# untitled.net
KiCad netlist of a schematic drawn in EAGLE
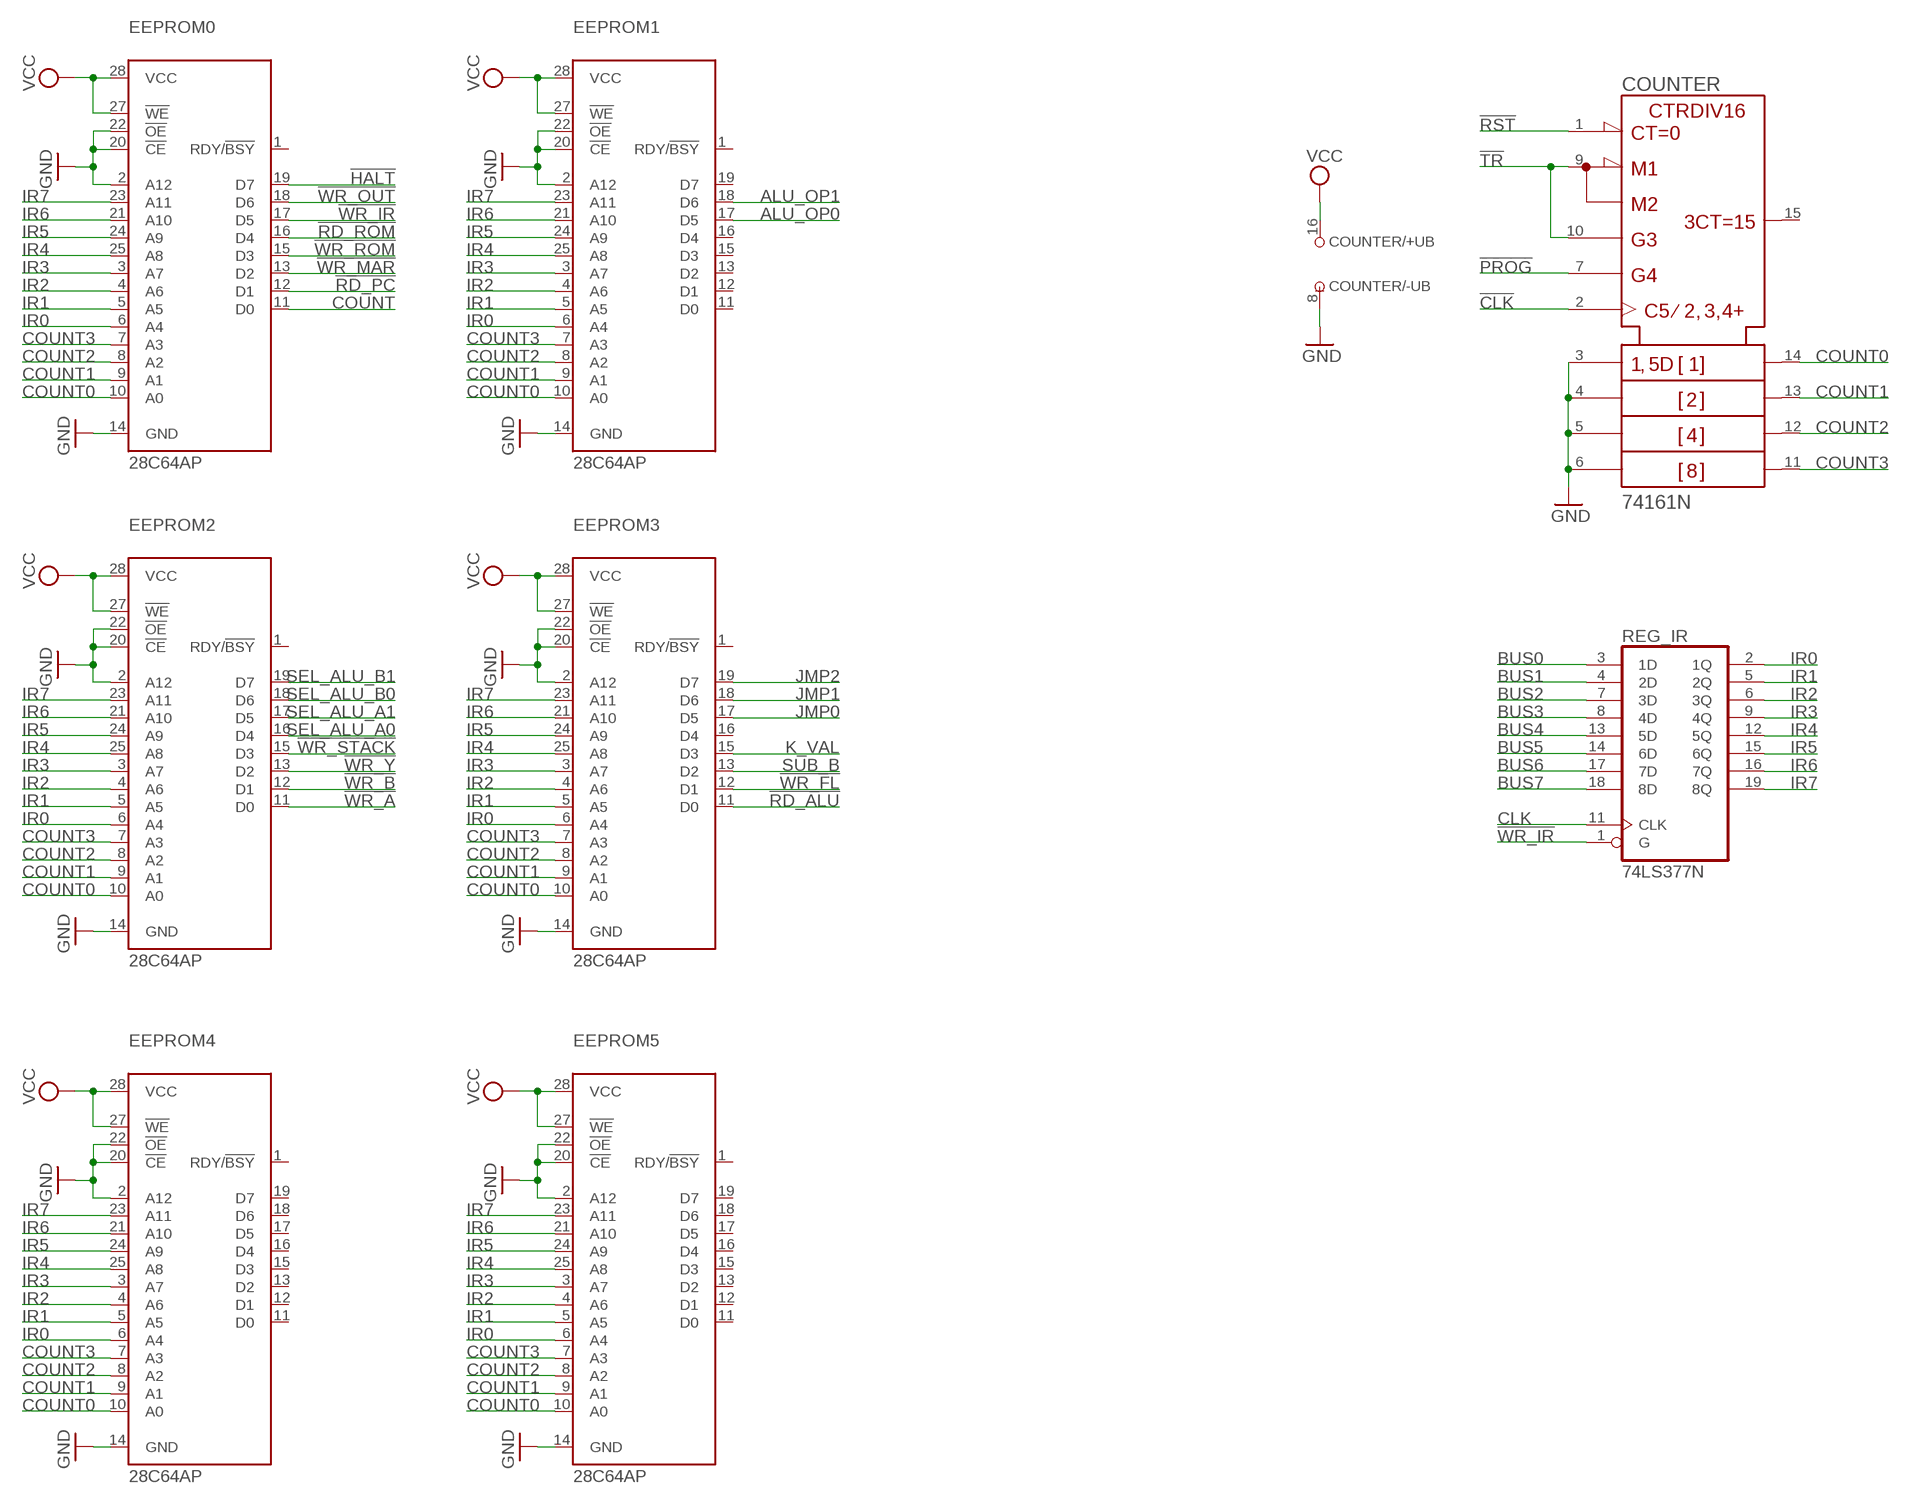
[diagram p0: schematic, sheet 1, part 1 of 2]
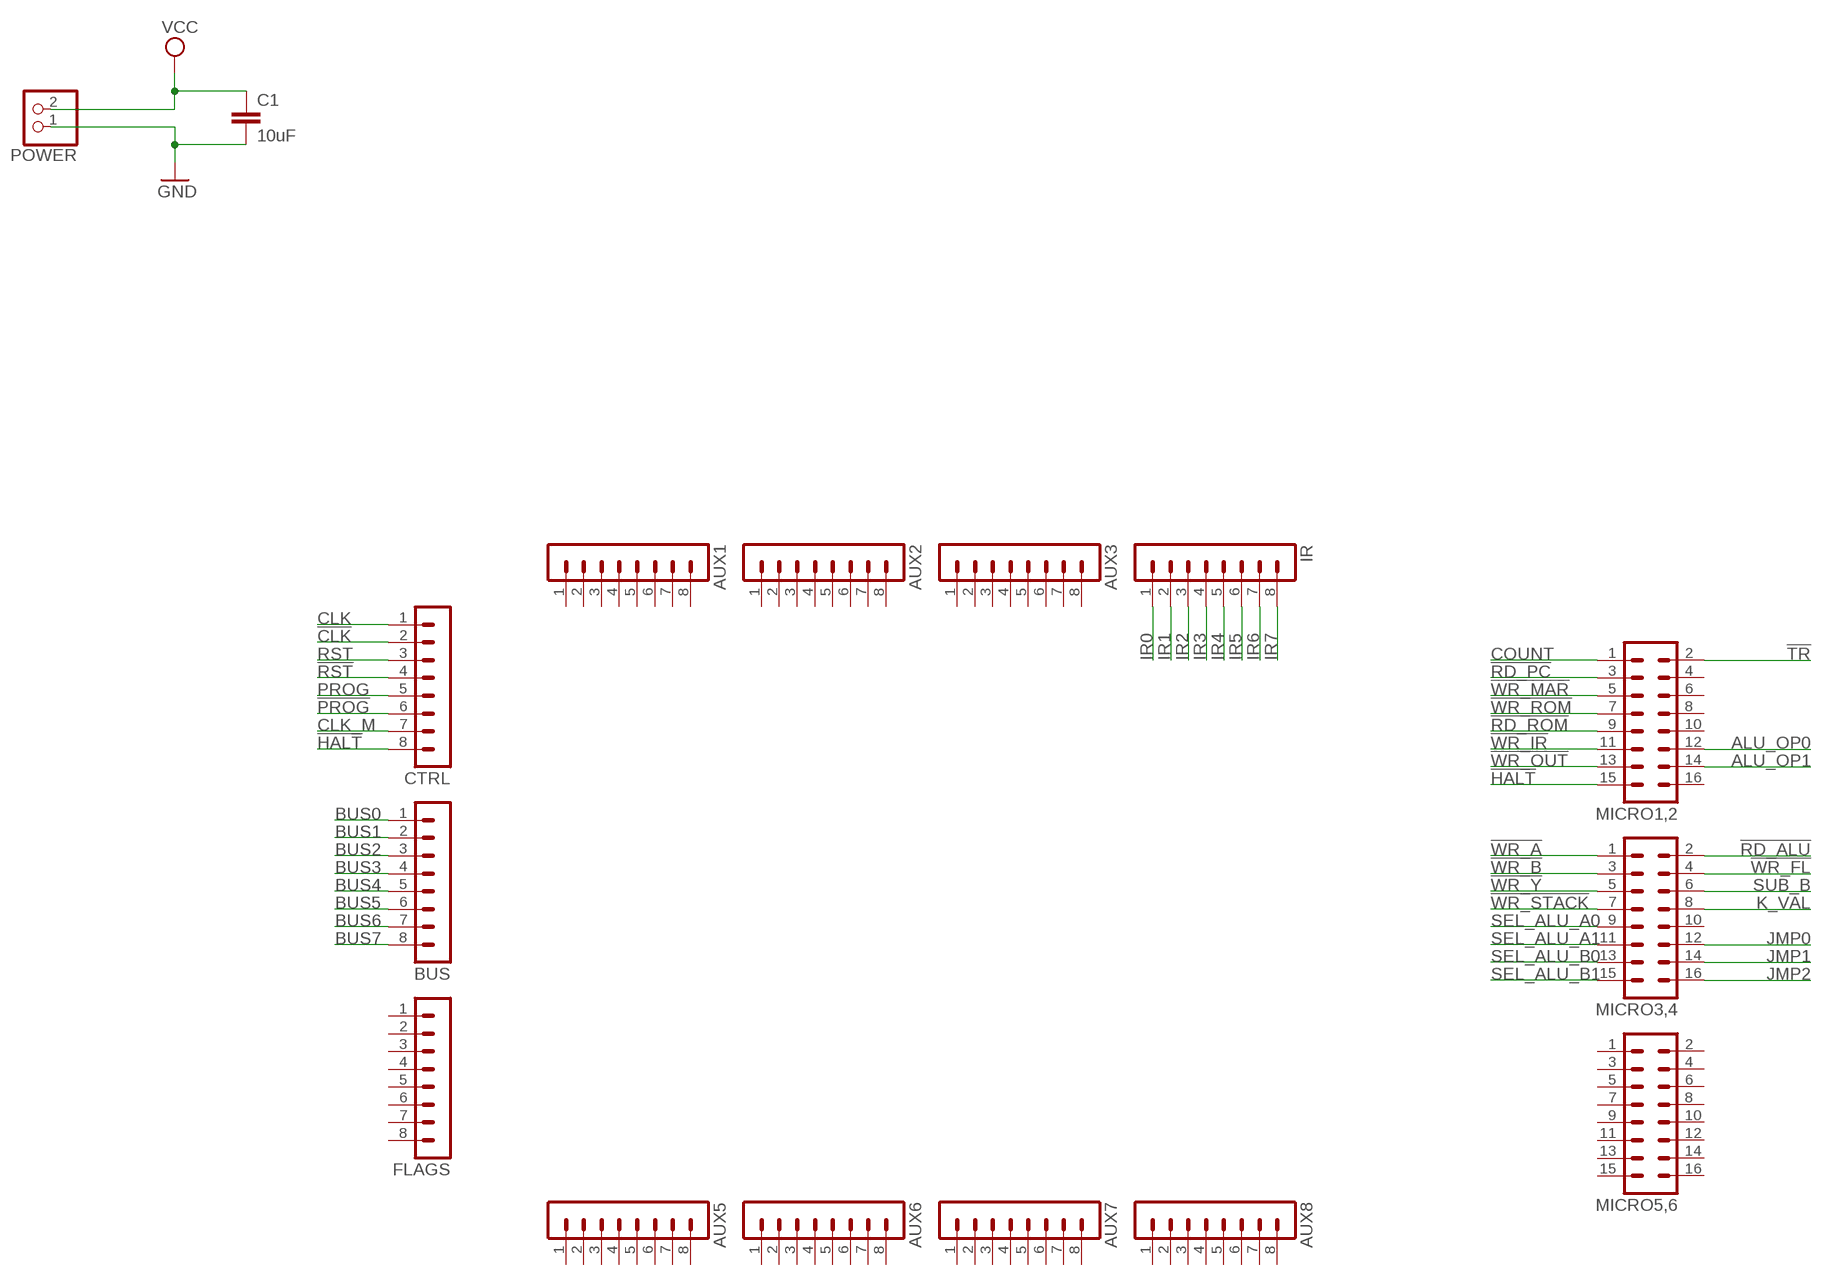
[diagram p1: schematic, sheet 1, part 2 of 2]

(export (version "E")
  (design (tool "Eeschema 10.0.6"))
  (components
    (comp (ref "AUX1")
      (value "MA08-1")
      (footprint "eagle-import:MA08-1")
      (libsource (lib "eagle-import") (part "MA08-1"))
    )
    (comp (ref "AUX2")
      (value "MA08-1")
      (footprint "eagle-import:MA08-1")
      (libsource (lib "eagle-import") (part "MA08-1"))
    )
    (comp (ref "AUX3")
      (value "MA08-1")
      (footprint "eagle-import:MA08-1")
      (libsource (lib "eagle-import") (part "MA08-1"))
    )
    (comp (ref "AUX5")
      (value "MA08-1")
      (footprint "eagle-import:MA08-1")
      (libsource (lib "eagle-import") (part "MA08-1"))
    )
    (comp (ref "AUX6")
      (value "MA08-1")
      (footprint "eagle-import:MA08-1")
      (libsource (lib "eagle-import") (part "MA08-1"))
    )
    (comp (ref "AUX7")
      (value "MA08-1")
      (footprint "eagle-import:MA08-1")
      (libsource (lib "eagle-import") (part "MA08-1"))
    )
    (comp (ref "AUX8")
      (value "MA08-1")
      (footprint "eagle-import:MA08-1")
      (libsource (lib "eagle-import") (part "MA08-1"))
    )
    (comp (ref "BUS")
      (value "MA08-1")
      (footprint "eagle-import:MA08-1")
      (libsource (lib "eagle-import") (part "MA08-1"))
    )
    (comp (ref "C1")
      (value "10uF")
      (footprint "eagle-import:C025-050X050")
      (libsource (lib "eagle-import") (part "C-EU025-050X050"))
    )
    (comp (ref "COUNTER")
      (value "74161N")
      (footprint "eagle-import:DIL16")
      (libsource (lib "eagle-import") (part "74161N"))
    )
    (comp (ref "CTRL")
      (value "MA08-1")
      (footprint "eagle-import:MA08-1")
      (libsource (lib "eagle-import") (part "MA08-1"))
    )
    (comp (ref "EEPROM0")
      (value "28C64AP")
      (footprint "eagle-import:DIL28-6")
      (fields (field (name "MPN") "AT28C64B-15PU"))
      (libsource (lib "eagle-import") (part "2864APC"))
    )
    (comp (ref "EEPROM1")
      (value "28C64AP")
      (footprint "eagle-import:DIL28-6")
      (fields (field (name "MPN") "AT28C64B-15PU"))
      (libsource (lib "eagle-import") (part "2864APC"))
    )
    (comp (ref "EEPROM2")
      (value "28C64AP")
      (footprint "eagle-import:DIL28-6")
      (fields (field (name "MPN") "AT28C64B-15PU"))
      (libsource (lib "eagle-import") (part "2864APC"))
    )
    (comp (ref "EEPROM3")
      (value "28C64AP")
      (footprint "eagle-import:DIL28-6")
      (fields (field (name "MPN") "AT28C64B-15PU"))
      (libsource (lib "eagle-import") (part "2864APC"))
    )
    (comp (ref "EEPROM4")
      (value "28C64AP")
      (footprint "eagle-import:DIL28-6")
      (fields (field (name "MPN") "AT28C64B-15PU"))
      (libsource (lib "eagle-import") (part "2864APC"))
    )
    (comp (ref "EEPROM5")
      (value "28C64AP")
      (footprint "eagle-import:DIL28-6")
      (fields (field (name "MPN") "AT28C64B-15PU"))
      (libsource (lib "eagle-import") (part "2864APC"))
    )
    (comp (ref "FLAGS")
      (value "MA08-1")
      (footprint "eagle-import:MA08-1")
      (libsource (lib "eagle-import") (part "MA08-1"))
    )
    (comp (ref "IR")
      (value "MA08-1")
      (footprint "eagle-import:MA08-1")
      (libsource (lib "eagle-import") (part "MA08-1"))
    )
    (comp (ref "MICRO1,2")
      (value "MA08-2")
      (footprint "eagle-import:MA08-2")
      (libsource (lib "eagle-import") (part "MA08-2"))
    )
    (comp (ref "MICRO3,4")
      (value "MA08-2")
      (footprint "eagle-import:MA08-2")
      (libsource (lib "eagle-import") (part "MA08-2"))
    )
    (comp (ref "MICRO5,6")
      (value "MA08-2")
      (footprint "eagle-import:MA08-2")
      (libsource (lib "eagle-import") (part "MA08-2"))
    )
    (comp (ref "POWER")
      (value "PINHD-1X2")
      (footprint "eagle-import:1X02")
      (libsource (lib "eagle-import") (part "PINHD-1X2"))
    )
    (comp (ref "REG_IR")
      (value "74LS377N")
      (footprint "eagle-import:DIL20")
      (libsource (lib "eagle-import") (part "74377NLS"))
    )
  )
  (nets
    (net (code "1") (name "ALU_OP0") (class "Default")
      (node (ref "EEPROM1") (pin "17") (pinfunction "D5_17") (pintype "tri_state"))
      (node (ref "MICRO1,2") (pin "12") (pinfunction "12_12") (pintype "passive"))
    )
    (net (code "2") (name "ALU_OP1") (class "Default")
      (node (ref "EEPROM1") (pin "18") (pinfunction "D6_18") (pintype "tri_state"))
      (node (ref "MICRO1,2") (pin "14") (pinfunction "14_14") (pintype "passive"))
    )
    (net (code "3") (name "BUS0") (class "Default")
      (node (ref "BUS") (pin "1") (pinfunction "1_1") (pintype "passive"))
      (node (ref "REG_IR") (pin "3") (pinfunction "1D_3") (pintype "input"))
    )
    (net (code "4") (name "BUS1") (class "Default")
      (node (ref "BUS") (pin "2") (pinfunction "2_2") (pintype "passive"))
      (node (ref "REG_IR") (pin "4") (pinfunction "2D_4") (pintype "input"))
    )
    (net (code "5") (name "BUS2") (class "Default")
      (node (ref "BUS") (pin "3") (pinfunction "3_3") (pintype "passive"))
      (node (ref "REG_IR") (pin "7") (pinfunction "3D_7") (pintype "input"))
    )
    (net (code "6") (name "BUS3") (class "Default")
      (node (ref "BUS") (pin "4") (pinfunction "4_4") (pintype "passive"))
      (node (ref "REG_IR") (pin "8") (pinfunction "4D_8") (pintype "input"))
    )
    (net (code "7") (name "BUS4") (class "Default")
      (node (ref "BUS") (pin "5") (pinfunction "5_5") (pintype "passive"))
      (node (ref "REG_IR") (pin "13") (pinfunction "5D_13") (pintype "input"))
    )
    (net (code "8") (name "BUS5") (class "Default")
      (node (ref "BUS") (pin "6") (pinfunction "6_6") (pintype "passive"))
      (node (ref "REG_IR") (pin "14") (pinfunction "6D_14") (pintype "input"))
    )
    (net (code "9") (name "BUS6") (class "Default")
      (node (ref "BUS") (pin "7") (pinfunction "7_7") (pintype "passive"))
      (node (ref "REG_IR") (pin "17") (pinfunction "7D_17") (pintype "input"))
    )
    (net (code "10") (name "BUS7") (class "Default")
      (node (ref "BUS") (pin "8") (pinfunction "8_8") (pintype "passive"))
      (node (ref "REG_IR") (pin "18") (pinfunction "8D_18") (pintype "input"))
    )
    (net (code "11") (name "CLK") (class "Default")
      (node (ref "CTRL") (pin "1") (pinfunction "1_1") (pintype "passive"))
      (node (ref "REG_IR") (pin "11") (pinfunction "CLK_11") (pintype "input"))
    )
    (net (code "12") (name "CLK_M") (class "Default")
      (node (ref "CTRL") (pin "7") (pinfunction "7_7") (pintype "passive"))
    )
    (net (code "13") (name "COUNT") (class "Default")
      (node (ref "EEPROM0") (pin "11") (pinfunction "D0_11") (pintype "tri_state"))
      (node (ref "MICRO1,2") (pin "1") (pinfunction "1_1") (pintype "passive"))
    )
    (net (code "14") (name "COUNT0") (class "Default")
      (node (ref "COUNTER") (pin "14") (pinfunction "QA_14") (pintype "output"))
      (node (ref "EEPROM0") (pin "10") (pinfunction "A0_10") (pintype "input"))
      (node (ref "EEPROM1") (pin "10") (pinfunction "A0_10") (pintype "input"))
      (node (ref "EEPROM2") (pin "10") (pinfunction "A0_10") (pintype "input"))
      (node (ref "EEPROM3") (pin "10") (pinfunction "A0_10") (pintype "input"))
      (node (ref "EEPROM4") (pin "10") (pinfunction "A0_10") (pintype "input"))
      (node (ref "EEPROM5") (pin "10") (pinfunction "A0_10") (pintype "input"))
    )
    (net (code "15") (name "COUNT1") (class "Default")
      (node (ref "COUNTER") (pin "13") (pinfunction "QB_13") (pintype "output"))
      (node (ref "EEPROM0") (pin "9") (pinfunction "A1_9") (pintype "input"))
      (node (ref "EEPROM1") (pin "9") (pinfunction "A1_9") (pintype "input"))
      (node (ref "EEPROM2") (pin "9") (pinfunction "A1_9") (pintype "input"))
      (node (ref "EEPROM3") (pin "9") (pinfunction "A1_9") (pintype "input"))
      (node (ref "EEPROM4") (pin "9") (pinfunction "A1_9") (pintype "input"))
      (node (ref "EEPROM5") (pin "9") (pinfunction "A1_9") (pintype "input"))
    )
    (net (code "16") (name "COUNT2") (class "Default")
      (node (ref "COUNTER") (pin "12") (pinfunction "QC_12") (pintype "output"))
      (node (ref "EEPROM0") (pin "8") (pinfunction "A2_8") (pintype "input"))
      (node (ref "EEPROM1") (pin "8") (pinfunction "A2_8") (pintype "input"))
      (node (ref "EEPROM2") (pin "8") (pinfunction "A2_8") (pintype "input"))
      (node (ref "EEPROM3") (pin "8") (pinfunction "A2_8") (pintype "input"))
      (node (ref "EEPROM4") (pin "8") (pinfunction "A2_8") (pintype "input"))
      (node (ref "EEPROM5") (pin "8") (pinfunction "A2_8") (pintype "input"))
    )
    (net (code "17") (name "COUNT3") (class "Default")
      (node (ref "COUNTER") (pin "11") (pinfunction "QD_11") (pintype "output"))
      (node (ref "EEPROM0") (pin "7") (pinfunction "A3_7") (pintype "input"))
      (node (ref "EEPROM1") (pin "7") (pinfunction "A3_7") (pintype "input"))
      (node (ref "EEPROM2") (pin "7") (pinfunction "A3_7") (pintype "input"))
      (node (ref "EEPROM3") (pin "7") (pinfunction "A3_7") (pintype "input"))
      (node (ref "EEPROM4") (pin "7") (pinfunction "A3_7") (pintype "input"))
      (node (ref "EEPROM5") (pin "7") (pinfunction "A3_7") (pintype "input"))
    )
    (net (code "18") (name "GND") (class "Default")
      (node (ref "C1") (pin "2") (pinfunction "2_2") (pintype "passive"))
      (node (ref "COUNTER") (pin "3") (pinfunction "A_3") (pintype "input"))
      (node (ref "COUNTER") (pin "4") (pinfunction "B_4") (pintype "input"))
      (node (ref "COUNTER") (pin "5") (pinfunction "C_5") (pintype "input"))
      (node (ref "COUNTER") (pin "6") (pinfunction "D_6") (pintype "input"))
      (node (ref "COUNTER") (pin "8") (pinfunction "-UB_8") (pintype "power_in"))
      (node (ref "EEPROM0") (pin "14") (pinfunction "GND_14") (pintype "power_in"))
      (node (ref "EEPROM0") (pin "2") (pinfunction "A12_2") (pintype "input"))
      (node (ref "EEPROM0") (pin "20") (pinfunction "~{CE}_20") (pintype "input"))
      (node (ref "EEPROM0") (pin "22") (pinfunction "~{OE}_22") (pintype "input"))
      (node (ref "EEPROM1") (pin "14") (pinfunction "GND_14") (pintype "power_in"))
      (node (ref "EEPROM1") (pin "2") (pinfunction "A12_2") (pintype "input"))
      (node (ref "EEPROM1") (pin "20") (pinfunction "~{CE}_20") (pintype "input"))
      (node (ref "EEPROM1") (pin "22") (pinfunction "~{OE}_22") (pintype "input"))
      (node (ref "EEPROM2") (pin "14") (pinfunction "GND_14") (pintype "power_in"))
      (node (ref "EEPROM2") (pin "2") (pinfunction "A12_2") (pintype "input"))
      (node (ref "EEPROM2") (pin "20") (pinfunction "~{CE}_20") (pintype "input"))
      (node (ref "EEPROM2") (pin "22") (pinfunction "~{OE}_22") (pintype "input"))
      (node (ref "EEPROM3") (pin "14") (pinfunction "GND_14") (pintype "power_in"))
      (node (ref "EEPROM3") (pin "2") (pinfunction "A12_2") (pintype "input"))
      (node (ref "EEPROM3") (pin "20") (pinfunction "~{CE}_20") (pintype "input"))
      (node (ref "EEPROM3") (pin "22") (pinfunction "~{OE}_22") (pintype "input"))
      (node (ref "EEPROM4") (pin "14") (pinfunction "GND_14") (pintype "power_in"))
      (node (ref "EEPROM4") (pin "2") (pinfunction "A12_2") (pintype "input"))
      (node (ref "EEPROM4") (pin "20") (pinfunction "~{CE}_20") (pintype "input"))
      (node (ref "EEPROM4") (pin "22") (pinfunction "~{OE}_22") (pintype "input"))
      (node (ref "EEPROM5") (pin "14") (pinfunction "GND_14") (pintype "power_in"))
      (node (ref "EEPROM5") (pin "2") (pinfunction "A12_2") (pintype "input"))
      (node (ref "EEPROM5") (pin "20") (pinfunction "~{CE}_20") (pintype "input"))
      (node (ref "EEPROM5") (pin "22") (pinfunction "~{OE}_22") (pintype "input"))
      (node (ref "POWER") (pin "1") (pinfunction "1_1") (pintype "passive"))
    )
    (net (code "19") (name "IR0") (class "Default")
      (node (ref "EEPROM0") (pin "6") (pinfunction "A4_6") (pintype "input"))
      (node (ref "EEPROM1") (pin "6") (pinfunction "A4_6") (pintype "input"))
      (node (ref "EEPROM2") (pin "6") (pinfunction "A4_6") (pintype "input"))
      (node (ref "EEPROM3") (pin "6") (pinfunction "A4_6") (pintype "input"))
      (node (ref "EEPROM4") (pin "6") (pinfunction "A4_6") (pintype "input"))
      (node (ref "EEPROM5") (pin "6") (pinfunction "A4_6") (pintype "input"))
      (node (ref "IR") (pin "1") (pinfunction "1_1") (pintype "passive"))
      (node (ref "REG_IR") (pin "2") (pinfunction "1Q_2") (pintype "output"))
    )
    (net (code "20") (name "IR1") (class "Default")
      (node (ref "EEPROM0") (pin "5") (pinfunction "A5_5") (pintype "input"))
      (node (ref "EEPROM1") (pin "5") (pinfunction "A5_5") (pintype "input"))
      (node (ref "EEPROM2") (pin "5") (pinfunction "A5_5") (pintype "input"))
      (node (ref "EEPROM3") (pin "5") (pinfunction "A5_5") (pintype "input"))
      (node (ref "EEPROM4") (pin "5") (pinfunction "A5_5") (pintype "input"))
      (node (ref "EEPROM5") (pin "5") (pinfunction "A5_5") (pintype "input"))
      (node (ref "IR") (pin "2") (pinfunction "2_2") (pintype "passive"))
      (node (ref "REG_IR") (pin "5") (pinfunction "2Q_5") (pintype "output"))
    )
    (net (code "21") (name "IR2") (class "Default")
      (node (ref "EEPROM0") (pin "4") (pinfunction "A6_4") (pintype "input"))
      (node (ref "EEPROM1") (pin "4") (pinfunction "A6_4") (pintype "input"))
      (node (ref "EEPROM2") (pin "4") (pinfunction "A6_4") (pintype "input"))
      (node (ref "EEPROM3") (pin "4") (pinfunction "A6_4") (pintype "input"))
      (node (ref "EEPROM4") (pin "4") (pinfunction "A6_4") (pintype "input"))
      (node (ref "EEPROM5") (pin "4") (pinfunction "A6_4") (pintype "input"))
      (node (ref "IR") (pin "3") (pinfunction "3_3") (pintype "passive"))
      (node (ref "REG_IR") (pin "6") (pinfunction "3Q_6") (pintype "output"))
    )
    (net (code "22") (name "IR3") (class "Default")
      (node (ref "EEPROM0") (pin "3") (pinfunction "A7_3") (pintype "input"))
      (node (ref "EEPROM1") (pin "3") (pinfunction "A7_3") (pintype "input"))
      (node (ref "EEPROM2") (pin "3") (pinfunction "A7_3") (pintype "input"))
      (node (ref "EEPROM3") (pin "3") (pinfunction "A7_3") (pintype "input"))
      (node (ref "EEPROM4") (pin "3") (pinfunction "A7_3") (pintype "input"))
      (node (ref "EEPROM5") (pin "3") (pinfunction "A7_3") (pintype "input"))
      (node (ref "IR") (pin "4") (pinfunction "4_4") (pintype "passive"))
      (node (ref "REG_IR") (pin "9") (pinfunction "4Q_9") (pintype "output"))
    )
    (net (code "23") (name "IR4") (class "Default")
      (node (ref "EEPROM0") (pin "25") (pinfunction "A8_25") (pintype "input"))
      (node (ref "EEPROM1") (pin "25") (pinfunction "A8_25") (pintype "input"))
      (node (ref "EEPROM2") (pin "25") (pinfunction "A8_25") (pintype "input"))
      (node (ref "EEPROM3") (pin "25") (pinfunction "A8_25") (pintype "input"))
      (node (ref "EEPROM4") (pin "25") (pinfunction "A8_25") (pintype "input"))
      (node (ref "EEPROM5") (pin "25") (pinfunction "A8_25") (pintype "input"))
      (node (ref "IR") (pin "5") (pinfunction "5_5") (pintype "passive"))
      (node (ref "REG_IR") (pin "12") (pinfunction "5Q_12") (pintype "output"))
    )
    (net (code "24") (name "IR5") (class "Default")
      (node (ref "EEPROM0") (pin "24") (pinfunction "A9_24") (pintype "input"))
      (node (ref "EEPROM1") (pin "24") (pinfunction "A9_24") (pintype "input"))
      (node (ref "EEPROM2") (pin "24") (pinfunction "A9_24") (pintype "input"))
      (node (ref "EEPROM3") (pin "24") (pinfunction "A9_24") (pintype "input"))
      (node (ref "EEPROM4") (pin "24") (pinfunction "A9_24") (pintype "input"))
      (node (ref "EEPROM5") (pin "24") (pinfunction "A9_24") (pintype "input"))
      (node (ref "IR") (pin "6") (pinfunction "6_6") (pintype "passive"))
      (node (ref "REG_IR") (pin "15") (pinfunction "6Q_15") (pintype "output"))
    )
    (net (code "25") (name "IR6") (class "Default")
      (node (ref "EEPROM0") (pin "21") (pinfunction "A10_21") (pintype "input"))
      (node (ref "EEPROM1") (pin "21") (pinfunction "A10_21") (pintype "input"))
      (node (ref "EEPROM2") (pin "21") (pinfunction "A10_21") (pintype "input"))
      (node (ref "EEPROM3") (pin "21") (pinfunction "A10_21") (pintype "input"))
      (node (ref "EEPROM4") (pin "21") (pinfunction "A10_21") (pintype "input"))
      (node (ref "EEPROM5") (pin "21") (pinfunction "A10_21") (pintype "input"))
      (node (ref "IR") (pin "7") (pinfunction "7_7") (pintype "passive"))
      (node (ref "REG_IR") (pin "16") (pinfunction "7Q_16") (pintype "output"))
    )
    (net (code "26") (name "IR7") (class "Default")
      (node (ref "EEPROM0") (pin "23") (pinfunction "A11_23") (pintype "input"))
      (node (ref "EEPROM1") (pin "23") (pinfunction "A11_23") (pintype "input"))
      (node (ref "EEPROM2") (pin "23") (pinfunction "A11_23") (pintype "input"))
      (node (ref "EEPROM3") (pin "23") (pinfunction "A11_23") (pintype "input"))
      (node (ref "EEPROM4") (pin "23") (pinfunction "A11_23") (pintype "input"))
      (node (ref "EEPROM5") (pin "23") (pinfunction "A11_23") (pintype "input"))
      (node (ref "IR") (pin "8") (pinfunction "8_8") (pintype "passive"))
      (node (ref "REG_IR") (pin "19") (pinfunction "8Q_19") (pintype "output"))
    )
    (net (code "27") (name "JMP0") (class "Default")
      (node (ref "EEPROM3") (pin "17") (pinfunction "D5_17") (pintype "tri_state"))
      (node (ref "MICRO3,4") (pin "12") (pinfunction "12_12") (pintype "passive"))
    )
    (net (code "28") (name "JMP1") (class "Default")
      (node (ref "EEPROM3") (pin "18") (pinfunction "D6_18") (pintype "tri_state"))
      (node (ref "MICRO3,4") (pin "14") (pinfunction "14_14") (pintype "passive"))
    )
    (net (code "29") (name "JMP2") (class "Default")
      (node (ref "EEPROM3") (pin "19") (pinfunction "D7_19") (pintype "tri_state"))
      (node (ref "MICRO3,4") (pin "16") (pinfunction "16_16") (pintype "passive"))
    )
    (net (code "30") (name "K_VAL") (class "Default")
      (node (ref "EEPROM3") (pin "15") (pinfunction "D3_15") (pintype "tri_state"))
      (node (ref "MICRO3,4") (pin "8") (pinfunction "8_8") (pintype "passive"))
    )
    (net (code "31") (name "PROG") (class "Default")
      (node (ref "CTRL") (pin "5") (pinfunction "5_5") (pintype "passive"))
    )
    (net (code "32") (name "RST") (class "Default")
      (node (ref "CTRL") (pin "3") (pinfunction "3_3") (pintype "passive"))
    )
    (net (code "33") (name "SEL_ALU_A0") (class "Default")
      (node (ref "EEPROM2") (pin "16") (pinfunction "D4_16") (pintype "tri_state"))
      (node (ref "MICRO3,4") (pin "9") (pinfunction "9_9") (pintype "passive"))
    )
    (net (code "34") (name "SEL_ALU_A1") (class "Default")
      (node (ref "EEPROM2") (pin "17") (pinfunction "D5_17") (pintype "tri_state"))
      (node (ref "MICRO3,4") (pin "11") (pinfunction "11_11") (pintype "passive"))
    )
    (net (code "35") (name "SEL_ALU_B0") (class "Default")
      (node (ref "EEPROM2") (pin "18") (pinfunction "D6_18") (pintype "tri_state"))
      (node (ref "MICRO3,4") (pin "13") (pinfunction "13_13") (pintype "passive"))
    )
    (net (code "36") (name "SEL_ALU_B1") (class "Default")
      (node (ref "EEPROM2") (pin "19") (pinfunction "D7_19") (pintype "tri_state"))
      (node (ref "MICRO3,4") (pin "15") (pinfunction "15_15") (pintype "passive"))
    )
    (net (code "37") (name "SUB_B") (class "Default")
      (node (ref "EEPROM3") (pin "13") (pinfunction "D2_13") (pintype "tri_state"))
      (node (ref "MICRO3,4") (pin "6") (pinfunction "6_6") (pintype "passive"))
    )
    (net (code "38") (name "VCC") (class "Default")
      (node (ref "C1") (pin "1") (pinfunction "1_1") (pintype "passive"))
      (node (ref "COUNTER") (pin "16") (pinfunction "+UB_16") (pintype "power_in"))
      (node (ref "EEPROM0") (pin "27") (pinfunction "~{WE}_27") (pintype "input"))
      (node (ref "EEPROM0") (pin "28") (pinfunction "VCC_28") (pintype "power_in"))
      (node (ref "EEPROM1") (pin "27") (pinfunction "~{WE}_27") (pintype "input"))
      (node (ref "EEPROM1") (pin "28") (pinfunction "VCC_28") (pintype "power_in"))
      (node (ref "EEPROM2") (pin "27") (pinfunction "~{WE}_27") (pintype "input"))
      (node (ref "EEPROM2") (pin "28") (pinfunction "VCC_28") (pintype "power_in"))
      (node (ref "EEPROM3") (pin "27") (pinfunction "~{WE}_27") (pintype "input"))
      (node (ref "EEPROM3") (pin "28") (pinfunction "VCC_28") (pintype "power_in"))
      (node (ref "EEPROM4") (pin "27") (pinfunction "~{WE}_27") (pintype "input"))
      (node (ref "EEPROM4") (pin "28") (pinfunction "VCC_28") (pintype "power_in"))
      (node (ref "EEPROM5") (pin "27") (pinfunction "~{WE}_27") (pintype "input"))
      (node (ref "EEPROM5") (pin "28") (pinfunction "VCC_28") (pintype "power_in"))
      (node (ref "POWER") (pin "2") (pinfunction "2_2") (pintype "passive"))
    )
    (net (code "39") (name "unconnected-(AUX1-Pad1)") (class "Default")
      (node (ref "AUX1") (pin "1") (pinfunction "1_1") (pintype "passive"))
    )
    (net (code "40") (name "unconnected-(AUX1-Pad2)") (class "Default")
      (node (ref "AUX1") (pin "2") (pinfunction "2_2") (pintype "passive"))
    )
    (net (code "41") (name "unconnected-(AUX1-Pad3)") (class "Default")
      (node (ref "AUX1") (pin "3") (pinfunction "3_3") (pintype "passive"))
    )
    (net (code "42") (name "unconnected-(AUX1-Pad4)") (class "Default")
      (node (ref "AUX1") (pin "4") (pinfunction "4_4") (pintype "passive"))
    )
    (net (code "43") (name "unconnected-(AUX1-Pad5)") (class "Default")
      (node (ref "AUX1") (pin "5") (pinfunction "5_5") (pintype "passive"))
    )
    (net (code "44") (name "unconnected-(AUX1-Pad6)") (class "Default")
      (node (ref "AUX1") (pin "6") (pinfunction "6_6") (pintype "passive"))
    )
    (net (code "45") (name "unconnected-(AUX1-Pad7)") (class "Default")
      (node (ref "AUX1") (pin "7") (pinfunction "7_7") (pintype "passive"))
    )
    (net (code "46") (name "unconnected-(AUX1-Pad8)") (class "Default")
      (node (ref "AUX1") (pin "8") (pinfunction "8_8") (pintype "passive"))
    )
    (net (code "47") (name "unconnected-(AUX2-Pad1)") (class "Default")
      (node (ref "AUX2") (pin "1") (pinfunction "1_1") (pintype "passive"))
    )
    (net (code "48") (name "unconnected-(AUX2-Pad2)") (class "Default")
      (node (ref "AUX2") (pin "2") (pinfunction "2_2") (pintype "passive"))
    )
    (net (code "49") (name "unconnected-(AUX2-Pad3)") (class "Default")
      (node (ref "AUX2") (pin "3") (pinfunction "3_3") (pintype "passive"))
    )
    (net (code "50") (name "unconnected-(AUX2-Pad4)") (class "Default")
      (node (ref "AUX2") (pin "4") (pinfunction "4_4") (pintype "passive"))
    )
    (net (code "51") (name "unconnected-(AUX2-Pad5)") (class "Default")
      (node (ref "AUX2") (pin "5") (pinfunction "5_5") (pintype "passive"))
    )
    (net (code "52") (name "unconnected-(AUX2-Pad6)") (class "Default")
      (node (ref "AUX2") (pin "6") (pinfunction "6_6") (pintype "passive"))
    )
    (net (code "53") (name "unconnected-(AUX2-Pad7)") (class "Default")
      (node (ref "AUX2") (pin "7") (pinfunction "7_7") (pintype "passive"))
    )
    (net (code "54") (name "unconnected-(AUX2-Pad8)") (class "Default")
      (node (ref "AUX2") (pin "8") (pinfunction "8_8") (pintype "passive"))
    )
    (net (code "55") (name "unconnected-(AUX3-Pad1)") (class "Default")
      (node (ref "AUX3") (pin "1") (pinfunction "1_1") (pintype "passive"))
    )
    (net (code "56") (name "unconnected-(AUX3-Pad2)") (class "Default")
      (node (ref "AUX3") (pin "2") (pinfunction "2_2") (pintype "passive"))
    )
    (net (code "57") (name "unconnected-(AUX3-Pad3)") (class "Default")
      (node (ref "AUX3") (pin "3") (pinfunction "3_3") (pintype "passive"))
    )
    (net (code "58") (name "unconnected-(AUX3-Pad4)") (class "Default")
      (node (ref "AUX3") (pin "4") (pinfunction "4_4") (pintype "passive"))
    )
    (net (code "59") (name "unconnected-(AUX3-Pad5)") (class "Default")
      (node (ref "AUX3") (pin "5") (pinfunction "5_5") (pintype "passive"))
    )
    (net (code "60") (name "unconnected-(AUX3-Pad6)") (class "Default")
      (node (ref "AUX3") (pin "6") (pinfunction "6_6") (pintype "passive"))
    )
    (net (code "61") (name "unconnected-(AUX3-Pad7)") (class "Default")
      (node (ref "AUX3") (pin "7") (pinfunction "7_7") (pintype "passive"))
    )
    (net (code "62") (name "unconnected-(AUX3-Pad8)") (class "Default")
      (node (ref "AUX3") (pin "8") (pinfunction "8_8") (pintype "passive"))
    )
    (net (code "63") (name "unconnected-(AUX5-Pad1)") (class "Default")
      (node (ref "AUX5") (pin "1") (pinfunction "1_1") (pintype "passive"))
    )
    (net (code "64") (name "unconnected-(AUX5-Pad2)") (class "Default")
      (node (ref "AUX5") (pin "2") (pinfunction "2_2") (pintype "passive"))
    )
    (net (code "65") (name "unconnected-(AUX5-Pad3)") (class "Default")
      (node (ref "AUX5") (pin "3") (pinfunction "3_3") (pintype "passive"))
    )
    (net (code "66") (name "unconnected-(AUX5-Pad4)") (class "Default")
      (node (ref "AUX5") (pin "4") (pinfunction "4_4") (pintype "passive"))
    )
    (net (code "67") (name "unconnected-(AUX5-Pad5)") (class "Default")
      (node (ref "AUX5") (pin "5") (pinfunction "5_5") (pintype "passive"))
    )
    (net (code "68") (name "unconnected-(AUX5-Pad6)") (class "Default")
      (node (ref "AUX5") (pin "6") (pinfunction "6_6") (pintype "passive"))
    )
    (net (code "69") (name "unconnected-(AUX5-Pad7)") (class "Default")
      (node (ref "AUX5") (pin "7") (pinfunction "7_7") (pintype "passive"))
    )
    (net (code "70") (name "unconnected-(AUX5-Pad8)") (class "Default")
      (node (ref "AUX5") (pin "8") (pinfunction "8_8") (pintype "passive"))
    )
    (net (code "71") (name "unconnected-(AUX6-Pad1)") (class "Default")
      (node (ref "AUX6") (pin "1") (pinfunction "1_1") (pintype "passive"))
    )
    (net (code "72") (name "unconnected-(AUX6-Pad2)") (class "Default")
      (node (ref "AUX6") (pin "2") (pinfunction "2_2") (pintype "passive"))
    )
    (net (code "73") (name "unconnected-(AUX6-Pad3)") (class "Default")
      (node (ref "AUX6") (pin "3") (pinfunction "3_3") (pintype "passive"))
    )
    (net (code "74") (name "unconnected-(AUX6-Pad4)") (class "Default")
      (node (ref "AUX6") (pin "4") (pinfunction "4_4") (pintype "passive"))
    )
    (net (code "75") (name "unconnected-(AUX6-Pad5)") (class "Default")
      (node (ref "AUX6") (pin "5") (pinfunction "5_5") (pintype "passive"))
    )
    (net (code "76") (name "unconnected-(AUX6-Pad6)") (class "Default")
      (node (ref "AUX6") (pin "6") (pinfunction "6_6") (pintype "passive"))
    )
    (net (code "77") (name "unconnected-(AUX6-Pad7)") (class "Default")
      (node (ref "AUX6") (pin "7") (pinfunction "7_7") (pintype "passive"))
    )
    (net (code "78") (name "unconnected-(AUX6-Pad8)") (class "Default")
      (node (ref "AUX6") (pin "8") (pinfunction "8_8") (pintype "passive"))
    )
    (net (code "79") (name "unconnected-(AUX7-Pad1)") (class "Default")
      (node (ref "AUX7") (pin "1") (pinfunction "1_1") (pintype "passive"))
    )
    (net (code "80") (name "unconnected-(AUX7-Pad2)") (class "Default")
      (node (ref "AUX7") (pin "2") (pinfunction "2_2") (pintype "passive"))
    )
    (net (code "81") (name "unconnected-(AUX7-Pad3)") (class "Default")
      (node (ref "AUX7") (pin "3") (pinfunction "3_3") (pintype "passive"))
    )
    (net (code "82") (name "unconnected-(AUX7-Pad4)") (class "Default")
      (node (ref "AUX7") (pin "4") (pinfunction "4_4") (pintype "passive"))
    )
    (net (code "83") (name "unconnected-(AUX7-Pad5)") (class "Default")
      (node (ref "AUX7") (pin "5") (pinfunction "5_5") (pintype "passive"))
    )
    (net (code "84") (name "unconnected-(AUX7-Pad6)") (class "Default")
      (node (ref "AUX7") (pin "6") (pinfunction "6_6") (pintype "passive"))
    )
    (net (code "85") (name "unconnected-(AUX7-Pad7)") (class "Default")
      (node (ref "AUX7") (pin "7") (pinfunction "7_7") (pintype "passive"))
    )
    (net (code "86") (name "unconnected-(AUX7-Pad8)") (class "Default")
      (node (ref "AUX7") (pin "8") (pinfunction "8_8") (pintype "passive"))
    )
    (net (code "87") (name "unconnected-(AUX8-Pad1)") (class "Default")
      (node (ref "AUX8") (pin "1") (pinfunction "1_1") (pintype "passive"))
    )
    (net (code "88") (name "unconnected-(AUX8-Pad2)") (class "Default")
      (node (ref "AUX8") (pin "2") (pinfunction "2_2") (pintype "passive"))
    )
    (net (code "89") (name "unconnected-(AUX8-Pad3)") (class "Default")
      (node (ref "AUX8") (pin "3") (pinfunction "3_3") (pintype "passive"))
    )
    (net (code "90") (name "unconnected-(AUX8-Pad4)") (class "Default")
      (node (ref "AUX8") (pin "4") (pinfunction "4_4") (pintype "passive"))
    )
    (net (code "91") (name "unconnected-(AUX8-Pad5)") (class "Default")
      (node (ref "AUX8") (pin "5") (pinfunction "5_5") (pintype "passive"))
    )
    (net (code "92") (name "unconnected-(AUX8-Pad6)") (class "Default")
      (node (ref "AUX8") (pin "6") (pinfunction "6_6") (pintype "passive"))
    )
    (net (code "93") (name "unconnected-(AUX8-Pad7)") (class "Default")
      (node (ref "AUX8") (pin "7") (pinfunction "7_7") (pintype "passive"))
    )
    (net (code "94") (name "unconnected-(AUX8-Pad8)") (class "Default")
      (node (ref "AUX8") (pin "8") (pinfunction "8_8") (pintype "passive"))
    )
    (net (code "95") (name "unconnected-(COUNTERC-RCO-Pad15)") (class "Default")
      (node (ref "COUNTER") (pin "15") (pinfunction "RCO_15") (pintype "output"))
    )
    (net (code "96") (name "unconnected-(EEPROM0-RDY{slash}~{BSY}-Pad1)") (class "Default")
      (node (ref "EEPROM0") (pin "1") (pinfunction "RDY/~{BSY}_1") (pintype "output"))
    )
    (net (code "97") (name "unconnected-(EEPROM1-D0-Pad11)") (class "Default")
      (node (ref "EEPROM1") (pin "11") (pinfunction "D0_11") (pintype "tri_state"))
    )
    (net (code "98") (name "unconnected-(EEPROM1-D1-Pad12)") (class "Default")
      (node (ref "EEPROM1") (pin "12") (pinfunction "D1_12") (pintype "tri_state"))
    )
    (net (code "99") (name "unconnected-(EEPROM1-D2-Pad13)") (class "Default")
      (node (ref "EEPROM1") (pin "13") (pinfunction "D2_13") (pintype "tri_state"))
    )
    (net (code "100") (name "unconnected-(EEPROM1-D3-Pad15)") (class "Default")
      (node (ref "EEPROM1") (pin "15") (pinfunction "D3_15") (pintype "tri_state"))
    )
    (net (code "101") (name "unconnected-(EEPROM1-D4-Pad16)") (class "Default")
      (node (ref "EEPROM1") (pin "16") (pinfunction "D4_16") (pintype "tri_state"))
    )
    (net (code "102") (name "unconnected-(EEPROM1-D7-Pad19)") (class "Default")
      (node (ref "EEPROM1") (pin "19") (pinfunction "D7_19") (pintype "tri_state"))
    )
    (net (code "103") (name "unconnected-(EEPROM1-RDY{slash}~{BSY}-Pad1)") (class "Default")
      (node (ref "EEPROM1") (pin "1") (pinfunction "RDY/~{BSY}_1") (pintype "output"))
    )
    (net (code "104") (name "unconnected-(EEPROM2-RDY{slash}~{BSY}-Pad1)") (class "Default")
      (node (ref "EEPROM2") (pin "1") (pinfunction "RDY/~{BSY}_1") (pintype "output"))
    )
    (net (code "105") (name "unconnected-(EEPROM3-D4-Pad16)") (class "Default")
      (node (ref "EEPROM3") (pin "16") (pinfunction "D4_16") (pintype "tri_state"))
    )
    (net (code "106") (name "unconnected-(EEPROM3-RDY{slash}~{BSY}-Pad1)") (class "Default")
      (node (ref "EEPROM3") (pin "1") (pinfunction "RDY/~{BSY}_1") (pintype "output"))
    )
    (net (code "107") (name "unconnected-(EEPROM4-D0-Pad11)") (class "Default")
      (node (ref "EEPROM4") (pin "11") (pinfunction "D0_11") (pintype "tri_state"))
    )
    (net (code "108") (name "unconnected-(EEPROM4-D1-Pad12)") (class "Default")
      (node (ref "EEPROM4") (pin "12") (pinfunction "D1_12") (pintype "tri_state"))
    )
    (net (code "109") (name "unconnected-(EEPROM4-D2-Pad13)") (class "Default")
      (node (ref "EEPROM4") (pin "13") (pinfunction "D2_13") (pintype "tri_state"))
    )
    (net (code "110") (name "unconnected-(EEPROM4-D3-Pad15)") (class "Default")
      (node (ref "EEPROM4") (pin "15") (pinfunction "D3_15") (pintype "tri_state"))
    )
    (net (code "111") (name "unconnected-(EEPROM4-D4-Pad16)") (class "Default")
      (node (ref "EEPROM4") (pin "16") (pinfunction "D4_16") (pintype "tri_state"))
    )
    (net (code "112") (name "unconnected-(EEPROM4-D5-Pad17)") (class "Default")
      (node (ref "EEPROM4") (pin "17") (pinfunction "D5_17") (pintype "tri_state"))
    )
    (net (code "113") (name "unconnected-(EEPROM4-D6-Pad18)") (class "Default")
      (node (ref "EEPROM4") (pin "18") (pinfunction "D6_18") (pintype "tri_state"))
    )
    (net (code "114") (name "unconnected-(EEPROM4-D7-Pad19)") (class "Default")
      (node (ref "EEPROM4") (pin "19") (pinfunction "D7_19") (pintype "tri_state"))
    )
    (net (code "115") (name "unconnected-(EEPROM4-RDY{slash}~{BSY}-Pad1)") (class "Default")
      (node (ref "EEPROM4") (pin "1") (pinfunction "RDY/~{BSY}_1") (pintype "output"))
    )
    (net (code "116") (name "unconnected-(EEPROM5-D0-Pad11)") (class "Default")
      (node (ref "EEPROM5") (pin "11") (pinfunction "D0_11") (pintype "tri_state"))
    )
    (net (code "117") (name "unconnected-(EEPROM5-D1-Pad12)") (class "Default")
      (node (ref "EEPROM5") (pin "12") (pinfunction "D1_12") (pintype "tri_state"))
    )
    (net (code "118") (name "unconnected-(EEPROM5-D2-Pad13)") (class "Default")
      (node (ref "EEPROM5") (pin "13") (pinfunction "D2_13") (pintype "tri_state"))
    )
    (net (code "119") (name "unconnected-(EEPROM5-D3-Pad15)") (class "Default")
      (node (ref "EEPROM5") (pin "15") (pinfunction "D3_15") (pintype "tri_state"))
    )
    (net (code "120") (name "unconnected-(EEPROM5-D4-Pad16)") (class "Default")
      (node (ref "EEPROM5") (pin "16") (pinfunction "D4_16") (pintype "tri_state"))
    )
    (net (code "121") (name "unconnected-(EEPROM5-D5-Pad17)") (class "Default")
      (node (ref "EEPROM5") (pin "17") (pinfunction "D5_17") (pintype "tri_state"))
    )
    (net (code "122") (name "unconnected-(EEPROM5-D6-Pad18)") (class "Default")
      (node (ref "EEPROM5") (pin "18") (pinfunction "D6_18") (pintype "tri_state"))
    )
    (net (code "123") (name "unconnected-(EEPROM5-D7-Pad19)") (class "Default")
      (node (ref "EEPROM5") (pin "19") (pinfunction "D7_19") (pintype "tri_state"))
    )
    (net (code "124") (name "unconnected-(EEPROM5-RDY{slash}~{BSY}-Pad1)") (class "Default")
      (node (ref "EEPROM5") (pin "1") (pinfunction "RDY/~{BSY}_1") (pintype "output"))
    )
    (net (code "125") (name "unconnected-(FLAGS-Pad1)") (class "Default")
      (node (ref "FLAGS") (pin "1") (pinfunction "1_1") (pintype "passive"))
    )
    (net (code "126") (name "unconnected-(FLAGS-Pad2)") (class "Default")
      (node (ref "FLAGS") (pin "2") (pinfunction "2_2") (pintype "passive"))
    )
    (net (code "127") (name "unconnected-(FLAGS-Pad3)") (class "Default")
      (node (ref "FLAGS") (pin "3") (pinfunction "3_3") (pintype "passive"))
    )
    (net (code "128") (name "unconnected-(FLAGS-Pad4)") (class "Default")
      (node (ref "FLAGS") (pin "4") (pinfunction "4_4") (pintype "passive"))
    )
    (net (code "129") (name "unconnected-(FLAGS-Pad5)") (class "Default")
      (node (ref "FLAGS") (pin "5") (pinfunction "5_5") (pintype "passive"))
    )
    (net (code "130") (name "unconnected-(FLAGS-Pad6)") (class "Default")
      (node (ref "FLAGS") (pin "6") (pinfunction "6_6") (pintype "passive"))
    )
    (net (code "131") (name "unconnected-(FLAGS-Pad7)") (class "Default")
      (node (ref "FLAGS") (pin "7") (pinfunction "7_7") (pintype "passive"))
    )
    (net (code "132") (name "unconnected-(FLAGS-Pad8)") (class "Default")
      (node (ref "FLAGS") (pin "8") (pinfunction "8_8") (pintype "passive"))
    )
    (net (code "133") (name "unconnected-(MICRO1,2-Pad4)") (class "Default")
      (node (ref "MICRO1,2") (pin "4") (pinfunction "4_4") (pintype "passive"))
    )
    (net (code "134") (name "unconnected-(MICRO1,2-Pad6)") (class "Default")
      (node (ref "MICRO1,2") (pin "6") (pinfunction "6_6") (pintype "passive"))
    )
    (net (code "135") (name "unconnected-(MICRO1,2-Pad8)") (class "Default")
      (node (ref "MICRO1,2") (pin "8") (pinfunction "8_8") (pintype "passive"))
    )
    (net (code "136") (name "unconnected-(MICRO1,2-Pad10)") (class "Default")
      (node (ref "MICRO1,2") (pin "10") (pinfunction "10_10") (pintype "passive"))
    )
    (net (code "137") (name "unconnected-(MICRO1,2-Pad16)") (class "Default")
      (node (ref "MICRO1,2") (pin "16") (pinfunction "16_16") (pintype "passive"))
    )
    (net (code "138") (name "unconnected-(MICRO3,4-Pad10)") (class "Default")
      (node (ref "MICRO3,4") (pin "10") (pinfunction "10_10") (pintype "passive"))
    )
    (net (code "139") (name "unconnected-(MICRO5,6-Pad1)") (class "Default")
      (node (ref "MICRO5,6") (pin "1") (pinfunction "1_1") (pintype "passive"))
    )
    (net (code "140") (name "unconnected-(MICRO5,6-Pad2)") (class "Default")
      (node (ref "MICRO5,6") (pin "2") (pinfunction "2_2") (pintype "passive"))
    )
    (net (code "141") (name "unconnected-(MICRO5,6-Pad3)") (class "Default")
      (node (ref "MICRO5,6") (pin "3") (pinfunction "3_3") (pintype "passive"))
    )
    (net (code "142") (name "unconnected-(MICRO5,6-Pad4)") (class "Default")
      (node (ref "MICRO5,6") (pin "4") (pinfunction "4_4") (pintype "passive"))
    )
    (net (code "143") (name "unconnected-(MICRO5,6-Pad5)") (class "Default")
      (node (ref "MICRO5,6") (pin "5") (pinfunction "5_5") (pintype "passive"))
    )
    (net (code "144") (name "unconnected-(MICRO5,6-Pad6)") (class "Default")
      (node (ref "MICRO5,6") (pin "6") (pinfunction "6_6") (pintype "passive"))
    )
    (net (code "145") (name "unconnected-(MICRO5,6-Pad7)") (class "Default")
      (node (ref "MICRO5,6") (pin "7") (pinfunction "7_7") (pintype "passive"))
    )
    (net (code "146") (name "unconnected-(MICRO5,6-Pad8)") (class "Default")
      (node (ref "MICRO5,6") (pin "8") (pinfunction "8_8") (pintype "passive"))
    )
    (net (code "147") (name "unconnected-(MICRO5,6-Pad9)") (class "Default")
      (node (ref "MICRO5,6") (pin "9") (pinfunction "9_9") (pintype "passive"))
    )
    (net (code "148") (name "unconnected-(MICRO5,6-Pad10)") (class "Default")
      (node (ref "MICRO5,6") (pin "10") (pinfunction "10_10") (pintype "passive"))
    )
    (net (code "149") (name "unconnected-(MICRO5,6-Pad11)") (class "Default")
      (node (ref "MICRO5,6") (pin "11") (pinfunction "11_11") (pintype "passive"))
    )
    (net (code "150") (name "unconnected-(MICRO5,6-Pad12)") (class "Default")
      (node (ref "MICRO5,6") (pin "12") (pinfunction "12_12") (pintype "passive"))
    )
    (net (code "151") (name "unconnected-(MICRO5,6-Pad13)") (class "Default")
      (node (ref "MICRO5,6") (pin "13") (pinfunction "13_13") (pintype "passive"))
    )
    (net (code "152") (name "unconnected-(MICRO5,6-Pad14)") (class "Default")
      (node (ref "MICRO5,6") (pin "14") (pinfunction "14_14") (pintype "passive"))
    )
    (net (code "153") (name "unconnected-(MICRO5,6-Pad15)") (class "Default")
      (node (ref "MICRO5,6") (pin "15") (pinfunction "15_15") (pintype "passive"))
    )
    (net (code "154") (name "unconnected-(MICRO5,6-Pad16)") (class "Default")
      (node (ref "MICRO5,6") (pin "16") (pinfunction "16_16") (pintype "passive"))
    )
    (net (code "155") (name "~{CLK}") (class "Default")
      (node (ref "COUNTER") (pin "2") (pinfunction "CLK_2") (pintype "input"))
      (node (ref "CTRL") (pin "2") (pinfunction "2_2") (pintype "passive"))
    )
    (net (code "156") (name "~{HALT}") (class "Default")
      (node (ref "CTRL") (pin "8") (pinfunction "8_8") (pintype "passive"))
      (node (ref "EEPROM0") (pin "19") (pinfunction "D7_19") (pintype "tri_state"))
      (node (ref "MICRO1,2") (pin "15") (pinfunction "15_15") (pintype "passive"))
    )
    (net (code "157") (name "~{PROG}") (class "Default")
      (node (ref "COUNTER") (pin "7") (pinfunction "ENP_7") (pintype "input"))
      (node (ref "CTRL") (pin "6") (pinfunction "6_6") (pintype "passive"))
    )
    (net (code "158") (name "~{RD_ALU}") (class "Default")
      (node (ref "EEPROM3") (pin "11") (pinfunction "D0_11") (pintype "tri_state"))
      (node (ref "MICRO3,4") (pin "2") (pinfunction "2_2") (pintype "passive"))
    )
    (net (code "159") (name "~{RD_PC}") (class "Default")
      (node (ref "EEPROM0") (pin "12") (pinfunction "D1_12") (pintype "tri_state"))
      (node (ref "MICRO1,2") (pin "3") (pinfunction "3_3") (pintype "passive"))
    )
    (net (code "160") (name "~{RD_ROM}") (class "Default")
      (node (ref "EEPROM0") (pin "16") (pinfunction "D4_16") (pintype "tri_state"))
      (node (ref "MICRO1,2") (pin "9") (pinfunction "9_9") (pintype "passive"))
    )
    (net (code "161") (name "~{RST}") (class "Default")
      (node (ref "COUNTER") (pin "1") (pinfunction "~{CLR}_1") (pintype "input"))
      (node (ref "CTRL") (pin "4") (pinfunction "4_4") (pintype "passive"))
    )
    (net (code "162") (name "~{TR}") (class "Default")
      (node (ref "COUNTER") (pin "10") (pinfunction "ENT_10") (pintype "input"))
      (node (ref "COUNTER") (pin "9") (pinfunction "~{LOAD}_9") (pintype "input"))
      (node (ref "MICRO1,2") (pin "2") (pinfunction "2_2") (pintype "passive"))
    )
    (net (code "163") (name "~{WR_A}") (class "Default")
      (node (ref "EEPROM2") (pin "11") (pinfunction "D0_11") (pintype "tri_state"))
      (node (ref "MICRO3,4") (pin "1") (pinfunction "1_1") (pintype "passive"))
    )
    (net (code "164") (name "~{WR_B}") (class "Default")
      (node (ref "EEPROM2") (pin "12") (pinfunction "D1_12") (pintype "tri_state"))
      (node (ref "MICRO3,4") (pin "3") (pinfunction "3_3") (pintype "passive"))
    )
    (net (code "165") (name "~{WR_FL}") (class "Default")
      (node (ref "EEPROM3") (pin "12") (pinfunction "D1_12") (pintype "tri_state"))
      (node (ref "MICRO3,4") (pin "4") (pinfunction "4_4") (pintype "passive"))
    )
    (net (code "166") (name "~{WR_IR}") (class "Default")
      (node (ref "EEPROM0") (pin "17") (pinfunction "D5_17") (pintype "tri_state"))
      (node (ref "MICRO1,2") (pin "11") (pinfunction "11_11") (pintype "passive"))
      (node (ref "REG_IR") (pin "1") (pinfunction "G_1") (pintype "input"))
    )
    (net (code "167") (name "~{WR_MAR}") (class "Default")
      (node (ref "EEPROM0") (pin "13") (pinfunction "D2_13") (pintype "tri_state"))
      (node (ref "MICRO1,2") (pin "5") (pinfunction "5_5") (pintype "passive"))
    )
    (net (code "168") (name "~{WR_OUT}") (class "Default")
      (node (ref "EEPROM0") (pin "18") (pinfunction "D6_18") (pintype "tri_state"))
      (node (ref "MICRO1,2") (pin "13") (pinfunction "13_13") (pintype "passive"))
    )
    (net (code "169") (name "~{WR_ROM}") (class "Default")
      (node (ref "EEPROM0") (pin "15") (pinfunction "D3_15") (pintype "tri_state"))
      (node (ref "MICRO1,2") (pin "7") (pinfunction "7_7") (pintype "passive"))
    )
    (net (code "170") (name "~{WR_STACK}") (class "Default")
      (node (ref "EEPROM2") (pin "15") (pinfunction "D3_15") (pintype "tri_state"))
      (node (ref "MICRO3,4") (pin "7") (pinfunction "7_7") (pintype "passive"))
    )
    (net (code "171") (name "~{WR_Y}") (class "Default")
      (node (ref "EEPROM2") (pin "13") (pinfunction "D2_13") (pintype "tri_state"))
      (node (ref "MICRO3,4") (pin "5") (pinfunction "5_5") (pintype "passive"))
    )
  )
)
